# Sheet1.net
KiCad netlist of a schematic drawn in Altium Designer
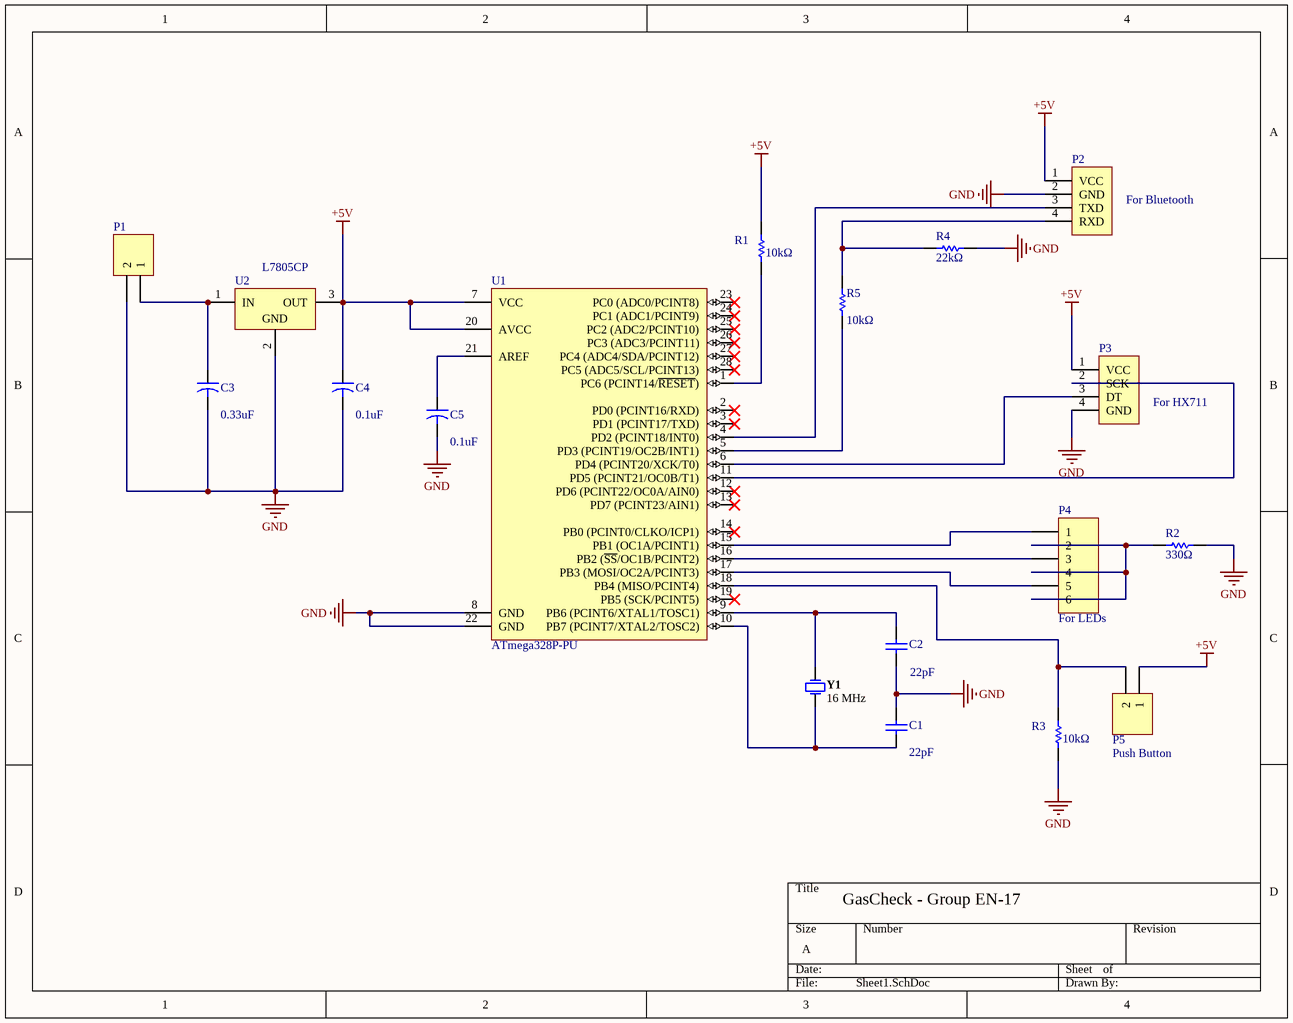
[diagram p0: Sheet1.SchDoc]

(export (version "E")
  (design (tool "Eeschema 10.0.6"))
  (components
    (comp (ref "C1")
      (value "22pF")
      (footprint "RAD-0.3")
      (description "Capacitor")
      (fields (field (name "Comment") "Cap") (field (name "PUBLISHER") "Altium Limited"))
      (libsource (lib "Miscellaneous Devices") (part "Cap"))
    )
    (comp (ref "C2")
      (value "22pF")
      (footprint "RAD-0.3")
      (description "Capacitor")
      (fields (field (name "Comment") "Cap") (field (name "PUBLISHER") "Altium Limited"))
      (libsource (lib "Miscellaneous Devices") (part "Cap"))
    )
    (comp (ref "C3")
      (value "0.33uF")
      (footprint "CAPR5-4X5")
      (description "Capacitor")
      (fields (field (name "Comment") "Cap2") (field (name "PUBLISHER") "Altium Limited"))
      (libsource (lib "Miscellaneous Devices") (part "Cap2"))
    )
    (comp (ref "C4")
      (value "0.1uF")
      (footprint "CAPR5-4X5")
      (description "Capacitor")
      (fields (field (name "Comment") "Cap2") (field (name "PUBLISHER") "Altium Limited"))
      (libsource (lib "Miscellaneous Devices") (part "Cap2"))
    )
    (comp (ref "C5")
      (value "0.1uF")
      (footprint "CAPR5-4X5")
      (description "Capacitor")
      (fields (field (name "Comment") "Cap2") (field (name "PUBLISHER") "Altium Limited"))
      (libsource (lib "Miscellaneous Devices") (part "Cap2"))
    )
    (comp (ref "P1")
      (value "Connector")
      (footprint "HDR1X2")
      (description "Header, 2-Pin")
      (fields (field (name "PUBLISHER") "Altium Limited"))
      (libsource (lib "") (part "Header 2_1"))
    )
    (comp (ref "P2")
      (value "For Bluetooth")
      (footprint "HDR1X4")
      (description "Header, 4-Pin")
      (fields (field (name "PUBLISHER") "Altium Limited"))
      (libsource (lib "Miscellaneous Connectors") (part "Header 4"))
    )
    (comp (ref "P3")
      (value "For HX711")
      (footprint "HDR1X4")
      (description "Header, 4-Pin")
      (fields (field (name "PUBLISHER") "Altium Limited"))
      (libsource (lib "Miscellaneous Connectors") (part "Header 4"))
    )
    (comp (ref "P4")
      (value "For LEDs")
      (footprint "HDR1X6")
      (description "Header, 6-Pin")
      (fields (field (name "PUBLISHER") "Altium Limited"))
      (libsource (lib "Miscellaneous Connectors") (part "Header 6"))
    )
    (comp (ref "P5")
      (value "Push Button")
      (footprint "HDR1X2")
      (description "Header, 2-Pin")
      (fields (field (name "PUBLISHER") "Altium Limited"))
      (libsource (lib "Miscellaneous Connectors") (part "Header 2"))
    )
    (comp (ref "R1")
      (value "10kΩ")
      (footprint "AXIAL-0.3")
      (description "Resistor")
      (fields (field (name "Comment") "Res1") (field (name "PUBLISHER") "Altium Limited"))
      (libsource (lib "Miscellaneous Devices") (part "Res1"))
    )
    (comp (ref "R2")
      (value "330Ω")
      (footprint "AXIAL-0.3")
      (description "Resistor")
      (fields (field (name "Comment") "Res1") (field (name "PUBLISHER") "Altium Limited"))
      (libsource (lib "Miscellaneous Devices") (part "Res1"))
    )
    (comp (ref "R3")
      (value "10kΩ")
      (footprint "AXIAL-0.3")
      (description "Resistor")
      (fields (field (name "Comment") "Res1") (field (name "PUBLISHER") "Altium Limited"))
      (libsource (lib "Miscellaneous Devices") (part "Res1"))
    )
    (comp (ref "R4")
      (value "22kΩ")
      (footprint "AXIAL-0.3")
      (description "Resistor")
      (fields (field (name "Comment") "Res1") (field (name "PUBLISHER") "Altium Limited"))
      (libsource (lib "Miscellaneous Devices") (part "Res1"))
    )
    (comp (ref "R5")
      (value "10kΩ")
      (footprint "AXIAL-0.3")
      (description "Resistor")
      (fields (field (name "Comment") "Res1") (field (name "PUBLISHER") "Altium Limited"))
      (libsource (lib "Miscellaneous Devices") (part "Res1"))
    )
    (comp (ref "U1")
      (value "ATmega328P-PU")
      (footprint "28P3")
      (libsource (lib "Altium Content Vault") (part "MC-8B-ATM48-IL28"))
    )
    (comp (ref "U2")
      (value "L7805CP")
      (footprint "TO220FP")
      (description "Positive Voltage Regulator, 5V, 3-Pin TO-220FP")
      (libsource (lib "Altium Content Vault") (part "PM-REG-L4940-SIL3"))
    )
    (comp (ref "Y1")
      (value "16 MHz")
      (footprint "FOX-FOXSLF160-20")
      (description "Resistance Weld Thru-Hole Crystal, 16 MHz, -20 to 70 degC, 2-Pin THD, RoHS, Bulk")
      (fields (field (name "TOLERANCE") "1%"))
      (libsource (lib "Altium Content Vault") (part "XTAL-1-2-2"))
    )
  )
  (nets
    (net (code "1") (name "+5V") (class "Default")
      (node (ref "C4") (pin "1") (pinfunction "1_1") (pintype "passive"))
      (node (ref "P2") (pin "1") (pinfunction "VCC_1") (pintype "passive"))
      (node (ref "P3") (pin "1") (pinfunction "VCC_1") (pintype "passive"))
      (node (ref "P5") (pin "1") (pinfunction "1_1") (pintype "passive"))
      (node (ref "R1") (pin "1") (pinfunction "1_1") (pintype "passive"))
      (node (ref "U1") (pin "20") (pinfunction "AVCC_20") (pintype "power_in"))
      (node (ref "U1") (pin "7") (pinfunction "VCC_7") (pintype "power_in"))
      (node (ref "U2") (pin "3") (pinfunction "OUT_3") (pintype "power_in"))
    )
    (net (code "2") (name "GND") (class "Default")
      (node (ref "C1") (pin "2") (pinfunction "2_2") (pintype "passive"))
      (node (ref "C2") (pin "2") (pinfunction "2_2") (pintype "passive"))
      (node (ref "C3") (pin "2") (pinfunction "2_2") (pintype "passive"))
      (node (ref "C4") (pin "2") (pinfunction "2_2") (pintype "passive"))
      (node (ref "C5") (pin "2") (pinfunction "2_2") (pintype "passive"))
      (node (ref "P1") (pin "2") (pinfunction "2_2") (pintype "passive"))
      (node (ref "P2") (pin "2") (pinfunction "SCK_2") (pintype "passive"))
      (node (ref "P3") (pin "4") (pinfunction "GND_4") (pintype "passive"))
      (node (ref "R2") (pin "2") (pinfunction "2_2") (pintype "passive"))
      (node (ref "R3") (pin "2") (pinfunction "2_2") (pintype "passive"))
      (node (ref "R4") (pin "2") (pinfunction "2_2") (pintype "passive"))
      (node (ref "U1") (pin "22") (pinfunction "GND_22") (pintype "power_in"))
      (node (ref "U1") (pin "8") (pinfunction "GND_8") (pintype "power_in"))
      (node (ref "U2") (pin "2") (pinfunction "GND_2") (pintype "power_in"))
    )
    (net (code "3") (name "Net-(P2-DT)") (class "Default")
      (node (ref "P2") (pin "3") (pinfunction "DT_3") (pintype "passive"))
      (node (ref "U1") (pin "4") (pinfunction "PD2_(PCINT18/INT0)_4") (pintype "bidirectional"))
    )
    (net (code "4") (name "Net-(P2-GND)") (class "Default")
      (node (ref "P2") (pin "4") (pinfunction "GND_4") (pintype "passive"))
      (node (ref "R4") (pin "1") (pinfunction "1_1") (pintype "passive"))
      (node (ref "R5") (pin "2") (pinfunction "2_2") (pintype "passive"))
    )
    (net (code "5") (name "Net-(P3-DT)") (class "Default")
      (node (ref "P3") (pin "3") (pinfunction "DT_3") (pintype "passive"))
      (node (ref "U1") (pin "6") (pinfunction "PD4_(PCINT20/XCK/T0)_6") (pintype "bidirectional"))
    )
    (net (code "6") (name "Net-(P3-SCK)") (class "Default")
      (node (ref "P3") (pin "2") (pinfunction "SCK_2") (pintype "passive"))
      (node (ref "U1") (pin "11") (pinfunction "PD5_(PCINT21/OC0B/T1)_11") (pintype "bidirectional"))
    )
    (net (code "7") (name "Net-(P4-Pad2)") (class "Default")
      (node (ref "P4") (pin "2") (pinfunction "2_2") (pintype "passive"))
      (node (ref "P4") (pin "4") (pinfunction "4_4") (pintype "passive"))
      (node (ref "P4") (pin "6") (pinfunction "6_6") (pintype "passive"))
      (node (ref "R2") (pin "1") (pinfunction "1_1") (pintype "passive"))
    )
    (net (code "8") (name "Net-(U1-AREF)") (class "Default")
      (node (ref "C5") (pin "1") (pinfunction "1_1") (pintype "passive"))
      (node (ref "U1") (pin "21") (pinfunction "AREF_21") (pintype "power_in"))
    )
    (net (code "9") (name "Net-(U1-PB1_(OC1A{slash}PCINT1))") (class "Default")
      (node (ref "P4") (pin "1") (pinfunction "1_1") (pintype "passive"))
      (node (ref "U1") (pin "15") (pinfunction "PB1_(OC1A/PCINT1)_15") (pintype "bidirectional"))
    )
    (net (code "10") (name "Net-(U1-PB2_(~{SS}{slash}OC1B{slash}PCINT2))") (class "Default")
      (node (ref "P4") (pin "3") (pinfunction "3_3") (pintype "passive"))
      (node (ref "U1") (pin "16") (pinfunction "PB2_(~{SS}/OC1B/PCINT2)_16") (pintype "bidirectional"))
    )
    (net (code "11") (name "Net-(U1-PB3_(MOSI{slash}OC2A{slash}PCINT3))") (class "Default")
      (node (ref "P4") (pin "5") (pinfunction "5_5") (pintype "passive"))
      (node (ref "U1") (pin "17") (pinfunction "PB3_(MOSI/OC2A/PCINT3)_17") (pintype "bidirectional"))
    )
    (net (code "12") (name "Net-(U1-PB4_(MISO{slash}PCINT4))") (class "Default")
      (node (ref "P5") (pin "2") (pinfunction "2_2") (pintype "passive"))
      (node (ref "R3") (pin "1") (pinfunction "1_1") (pintype "passive"))
      (node (ref "U1") (pin "18") (pinfunction "PB4_(MISO/PCINT4)_18") (pintype "bidirectional"))
    )
    (net (code "13") (name "Net-(U1-PB6_(PCINT6{slash}XTAL1{slash}TOSC1))") (class "Default")
      (node (ref "C2") (pin "1") (pinfunction "1_1") (pintype "passive"))
      (node (ref "U1") (pin "9") (pinfunction "PB6_(PCINT6/XTAL1/TOSC1)_9") (pintype "bidirectional"))
      (node (ref "Y1") (pin "1") (pinfunction "1_1") (pintype "passive"))
    )
    (net (code "14") (name "Net-(U1-PB7_(PCINT7{slash}XTAL2{slash}TOSC2))") (class "Default")
      (node (ref "C1") (pin "1") (pinfunction "1_1") (pintype "passive"))
      (node (ref "U1") (pin "10") (pinfunction "PB7_(PCINT7/XTAL2/TOSC2)_10") (pintype "bidirectional"))
      (node (ref "Y1") (pin "2") (pinfunction "2_2") (pintype "passive"))
    )
    (net (code "15") (name "Net-(U1-PC6_(PCINT14{slash}~{RESET}))") (class "Default")
      (node (ref "R1") (pin "2") (pinfunction "2_2") (pintype "passive"))
      (node (ref "U1") (pin "1") (pinfunction "PC6_(PCINT14/~{RESET})_1") (pintype "bidirectional"))
    )
    (net (code "16") (name "Net-(U1-PD3_(PCINT19{slash}OC2B{slash}INT1))") (class "Default")
      (node (ref "R5") (pin "1") (pinfunction "1_1") (pintype "passive"))
      (node (ref "U1") (pin "5") (pinfunction "PD3_(PCINT19/OC2B/INT1)_5") (pintype "bidirectional"))
    )
    (net (code "17") (name "Net-(U2-IN)") (class "Default")
      (node (ref "C3") (pin "1") (pinfunction "1_1") (pintype "passive"))
      (node (ref "P1") (pin "1") (pinfunction "1_1") (pintype "passive"))
      (node (ref "U2") (pin "1") (pinfunction "IN_1") (pintype "power_in"))
    )
    (net (code "18") (name "unconnected-(U1-PB0_(PCINT0{slash}CLKO{slash}ICP1)-Pad14)") (class "Default")
      (node (ref "U1") (pin "14") (pinfunction "PB0_(PCINT0/CLKO/ICP1)_14") (pintype "bidirectional+no_connect"))
    )
    (net (code "19") (name "unconnected-(U1-PB5_(SCK{slash}PCINT5)-Pad19)") (class "Default")
      (node (ref "U1") (pin "19") (pinfunction "PB5_(SCK/PCINT5)_19") (pintype "bidirectional+no_connect"))
    )
    (net (code "20") (name "unconnected-(U1-PC0_(ADC0{slash}PCINT8)-Pad23)") (class "Default")
      (node (ref "U1") (pin "23") (pinfunction "PC0_(ADC0/PCINT8)_23") (pintype "bidirectional+no_connect"))
    )
    (net (code "21") (name "unconnected-(U1-PC1_(ADC1{slash}PCINT9)-Pad24)") (class "Default")
      (node (ref "U1") (pin "24") (pinfunction "PC1_(ADC1/PCINT9)_24") (pintype "bidirectional+no_connect"))
    )
    (net (code "22") (name "unconnected-(U1-PC2_(ADC2{slash}PCINT10)-Pad25)") (class "Default")
      (node (ref "U1") (pin "25") (pinfunction "PC2_(ADC2/PCINT10)_25") (pintype "bidirectional+no_connect"))
    )
    (net (code "23") (name "unconnected-(U1-PC3_(ADC3{slash}PCINT11)-Pad26)") (class "Default")
      (node (ref "U1") (pin "26") (pinfunction "PC3_(ADC3/PCINT11)_26") (pintype "bidirectional+no_connect"))
    )
    (net (code "24") (name "unconnected-(U1-PC4_(ADC4{slash}SDA{slash}PCINT12)-Pad27)") (class "Default")
      (node (ref "U1") (pin "27") (pinfunction "PC4_(ADC4/SDA/PCINT12)_27") (pintype "bidirectional+no_connect"))
    )
    (net (code "25") (name "unconnected-(U1-PC5_(ADC5{slash}SCL{slash}PCINT13)-Pad28)") (class "Default")
      (node (ref "U1") (pin "28") (pinfunction "PC5_(ADC5/SCL/PCINT13)_28") (pintype "bidirectional+no_connect"))
    )
    (net (code "26") (name "unconnected-(U1-PD0_(PCINT16{slash}RXD)-Pad2)") (class "Default")
      (node (ref "U1") (pin "2") (pinfunction "PD0_(PCINT16/RXD)_2") (pintype "bidirectional+no_connect"))
    )
    (net (code "27") (name "unconnected-(U1-PD1_(PCINT17{slash}TXD)-Pad3)") (class "Default")
      (node (ref "U1") (pin "3") (pinfunction "PD1_(PCINT17/TXD)_3") (pintype "bidirectional+no_connect"))
    )
    (net (code "28") (name "unconnected-(U1-PD6_(PCINT22{slash}OC0A{slash}AIN0)-Pad12)") (class "Default")
      (node (ref "U1") (pin "12") (pinfunction "PD6_(PCINT22/OC0A/AIN0)_12") (pintype "bidirectional+no_connect"))
    )
    (net (code "29") (name "unconnected-(U1-PD7_(PCINT23{slash}AIN1)-Pad13)") (class "Default")
      (node (ref "U1") (pin "13") (pinfunction "PD7_(PCINT23/AIN1)_13") (pintype "bidirectional+no_connect"))
    )
  )
)
